# Battery_Management.net
KiCad netlist of a schematic drawn in Altium Designer
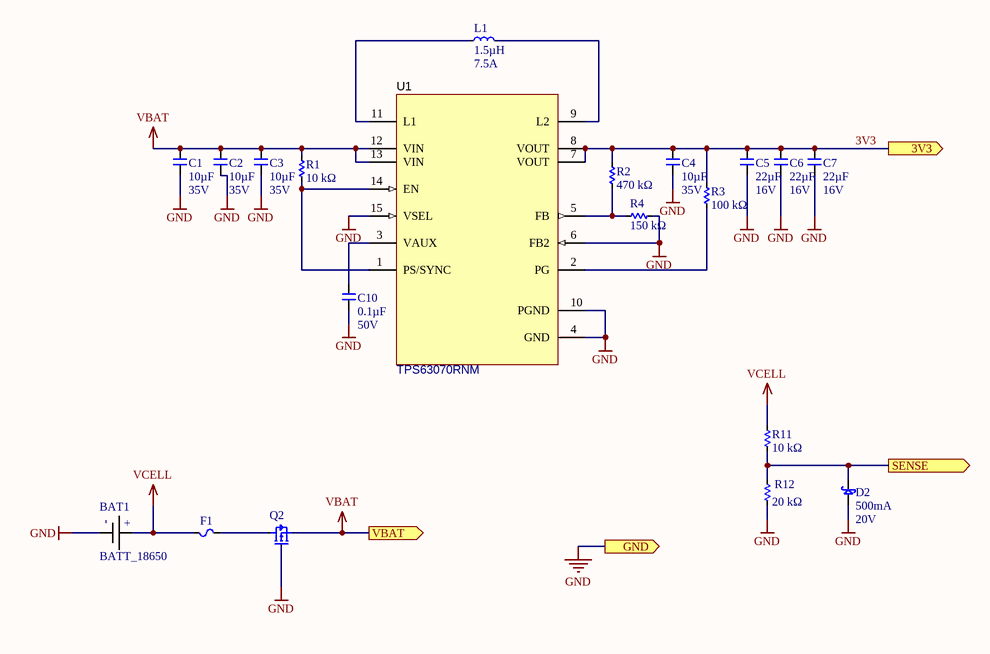
[diagram p0: Battery_Management.SchDoc]

(export (version "E")
  (design (tool "Eeschema 10.0.6"))
  (components
    (comp (ref "BAT1")
      (value "BATT_18650")
      (footprint "BATT_18650_KEYSTONE_1042_VIAS")
      (description "Dual Lithium Ion Cell Holder")
      (fields
        (field (name "MANUFACTURER") "Keystone Electronics")
        (field (name "MANUFACTURER PART NUMBER") "1048P")
      )
      (libsource (lib "Stanford Student Space Initiative") (part "BATT_18650"))
    )
    (comp (ref "C1")
      (value "490-13248-1-ND")
      (footprint "C0603")
      (description "CAP CER 10UF 35V X5R 0603 20%")
      (fields
        (field (name "CAPACITANCE (SHORTHAND)") "10µF")
        (field (name "RATED VOLTAGE") "35V")
        (field (name "MANUFACTURER") "Murata Electronics North America")
      )
      (libsource (lib "Stanford Student Space Initiative") (part "__template_cap"))
    )
    (comp (ref "C2")
      (value "490-13248-1-ND")
      (footprint "C0603")
      (description "CAP CER 10UF 35V X5R 0603 20%")
      (fields
        (field (name "CAPACITANCE (SHORTHAND)") "10µF")
        (field (name "RATED VOLTAGE") "35V")
        (field (name "MANUFACTURER") "Murata Electronics North America")
      )
      (libsource (lib "Stanford Student Space Initiative") (part "__template_cap"))
    )
    (comp (ref "C3")
      (value "490-13248-1-ND")
      (footprint "C0603")
      (description "CAP CER 10UF 35V X5R 0603 20%")
      (fields
        (field (name "CAPACITANCE (SHORTHAND)") "10µF")
        (field (name "RATED VOLTAGE") "35V")
        (field (name "MANUFACTURER") "Murata Electronics North America")
      )
      (libsource (lib "Stanford Student Space Initiative") (part "__template_cap"))
    )
    (comp (ref "C4")
      (value "490-13248-1-ND")
      (footprint "C0603")
      (description "CAP CER 10UF 35V X5R 0603 20%")
      (fields
        (field (name "CAPACITANCE (SHORTHAND)") "10µF")
        (field (name "RATED VOLTAGE") "35V")
        (field (name "MANUFACTURER") "Murata Electronics North America")
      )
      (libsource (lib "Stanford Student Space Initiative") (part "__template_cap"))
    )
    (comp (ref "C5")
      (value "1276-7076-1-ND")
      (footprint "C0603")
      (description "CAP CER 22UF 16V X5R 0603 20%")
      (fields
        (field (name "CAPACITANCE (SHORTHAND)") "22µF")
        (field (name "RATED VOLTAGE") "16V")
        (field (name "MANUFACTURER") "Samsung Electro-Mechanics")
      )
      (libsource (lib "Stanford Student Space Initiative") (part "__template_cap"))
    )
    (comp (ref "C6")
      (value "1276-7076-1-ND")
      (footprint "C0603")
      (description "CAP CER 22UF 16V X5R 0603 20%")
      (fields
        (field (name "CAPACITANCE (SHORTHAND)") "22µF")
        (field (name "RATED VOLTAGE") "16V")
        (field (name "MANUFACTURER") "Samsung Electro-Mechanics")
      )
      (libsource (lib "Stanford Student Space Initiative") (part "__template_cap"))
    )
    (comp (ref "C7")
      (value "1276-7076-1-ND")
      (footprint "C0603")
      (description "CAP CER 22UF 16V X5R 0603 20%")
      (fields
        (field (name "CAPACITANCE (SHORTHAND)") "22µF")
        (field (name "RATED VOLTAGE") "16V")
        (field (name "MANUFACTURER") "Samsung Electro-Mechanics")
      )
      (libsource (lib "Stanford Student Space Initiative") (part "__template_cap"))
    )
    (comp (ref "C10")
      (value "490-1519-1-ND")
      (footprint "C0603")
      (description "CAP CER 0603 0.1µF X7R 50V 10%")
      (fields
        (field (name "CAPACITANCE (SHORTHAND)") "0.1µF")
        (field (name "RATED VOLTAGE") "50V")
        (field (name "MANUFACTURER") "Murata Electronics North America")
      )
      (libsource (lib "Stanford Student Space Initiative") (part "__template_cap"))
    )
    (comp (ref "D2")
      (value "Symbol")
      (footprint "SOD123")
      (description "DIODE SCHOTTKY 0.5A 20V SOD-123")
      (fields
        (field (name "MANUFACTURER") "Fairchild Semiconductor")
        (field (name "MANUFACTURER PART NUMBER") "MBR0520L")
        (field (name "CURRENT - AVERAGE RECTIFIED (IO)") "500mA")
        (field (name "VOLTAGE - DC REVERSE (VR) (MAX)") "20V")
      )
      (libsource (lib "") (part "Symbol_2"))
    )
    (comp (ref "F1") (value "Symbol") (footprint "R1206") (libsource (lib "") (part "Symbol_1")))
    (comp (ref "L1")
      (value "Symbol")
      (footprint "SMD5230")
      (description "INDUCTOR POWER 1.5UH 7.5A SMD")
      (fields
        (field (name "MANUFACTURER") "Vishay Dale")
        (field (name "MANUFACTURER PART NUMBER") "IHLP2020CZER1R5M11")
        (field (name "INDUCTANCE") "1.5µH")
        (field (name "CURRENT RATING") "7.5A")
      )
      (libsource (lib "Stanford Student Space Initiative") (part "Symbol"))
    )
    (comp (ref "Q2")
      (value "PFET_SI7615ADN-T1")
      (footprint "POWERPAK_1212-8_SINGLE")
      (description "MOSFET P-CH 20V 35A PPK")
      (fields
        (field (name "MANUFACTURER PART NUMBER") "SI7615ADN-T1-GE3")
        (field (name "MANUFACTURER") "Vishay Siliconix")
      )
      (libsource (lib "Stanford Student Space Initiative") (part "PFET_SI7615ADN-T1"))
    )
    (comp (ref "R1")
      (value "311-10.0KHRCT-ND")
      (footprint "R0603")
      (description "RES SMD 10K OHM 1% 1/10W 0603")
      (fields
        (field (name "RESISTANCE") "10 kΩ")
        (field (name "MANUFACTURER PART NUMBER") "RC0603FR-0710KL")
        (field (name "MANUFACTURER") "Yageo")
      )
      (libsource (lib "Stanford Student Space Initiative") (part "__template_resistor"))
    )
    (comp (ref "R2")
      (value "311-470KHRCT-ND")
      (footprint "R0603")
      (description "RES SMD 470K OHM 1% 1/10W 0603")
      (fields
        (field (name "MANUFACTURER PART NUMBER") "RC0603FR-07470KL")
        (field (name "MANUFACTURER") "Yageo")
        (field (name "RESISTANCE") "470 kΩ")
      )
      (libsource (lib "Stanford Student Space Initiative") (part "__template_resistor"))
    )
    (comp (ref "R3")
      (value "311-100KHRCT-ND")
      (footprint "R0603")
      (description "RES SMD 100K OHM 1% 1/10W 0603")
      (fields
        (field (name "MANUFACTURER PART NUMBER") "RC0603FR-07100KL")
        (field (name "MANUFACTURER") "Yageo")
        (field (name "RESISTANCE") "100 kΩ")
      )
      (libsource (lib "Stanford Student Space Initiative") (part "__template_resistor"))
    )
    (comp (ref "R4")
      (value "311-150KHRCT-ND")
      (footprint "R0603")
      (description "RES SMD 150K OHM 1% 1/10W 0603")
      (fields
        (field (name "MANUFACTURER PART NUMBER") "RC0603FR-07150KL")
        (field (name "MANUFACTURER") "Yageo")
        (field (name "RESISTANCE") "150 kΩ")
      )
      (libsource (lib "Stanford Student Space Initiative") (part "__template_resistor"))
    )
    (comp (ref "R11")
      (value "311-10.0KHRCT-ND")
      (footprint "R0603")
      (description "RES SMD 10K OHM 1% 1/10W 0603")
      (fields
        (field (name "RESISTANCE") "10 kΩ")
        (field (name "MANUFACTURER PART NUMBER") "RC0603FR-0710KL")
        (field (name "MANUFACTURER") "Yageo")
      )
      (libsource (lib "Stanford Student Space Initiative") (part "__template_resistor"))
    )
    (comp (ref "R12")
      (value "311-20.0KHRCT-ND")
      (footprint "R0603")
      (description "RES SMD 20K OHM 1% 1/10W 0603")
      (fields
        (field (name "RESISTANCE") "20 kΩ")
        (field (name "MANUFACTURER PART NUMBER") "RC0603FR-0720KL")
        (field (name "MANUFACTURER") "Yageo")
      )
      (libsource (lib "Stanford Student Space Initiative") (part "__template_resistor"))
    )
    (comp (ref "U1")
      (value "TPS63070RNM")
      (footprint "TPS63070")
      (description "BUCKBOOST TPS63070RNM, RNM0015A")
      (fields
        (field (name "MANUFACTURER") "Texas Instruments")
        (field (name "MANUFACTURER PART NUMBER") "TPS63070RNMR")
      )
      (libsource (lib "Stanford Student Space Initiative") (part "TPS63070RNM"))
    )
  )
  (nets
    (net (code "1") (name "/3V3") (class "Default")
      (node (ref "C4") (pin "1") (pintype "passive"))
      (node (ref "C5") (pin "1") (pintype "passive"))
      (node (ref "C6") (pin "1") (pintype "passive"))
      (node (ref "C7") (pin "1") (pintype "passive"))
      (node (ref "R2") (pin "2") (pintype "passive"))
      (node (ref "R3") (pin "2") (pintype "passive"))
      (node (ref "U1") (pin "7") (pinfunction "VOUT_7") (pintype "power_in"))
      (node (ref "U1") (pin "8") (pinfunction "VOUT_8") (pintype "power_in"))
    )
    (net (code "2") (name "/SENSE") (class "Default")
      (node (ref "D2") (pin "2") (pintype "passive"))
      (node (ref "R11") (pin "1") (pintype "passive"))
      (node (ref "R12") (pin "2") (pintype "passive"))
    )
    (net (code "3") (name "GND") (class "Default")
      (node (ref "BAT1") (pin "CELL-") (pinfunction "CELL-_CELL-") (pintype "passive"))
      (node (ref "C1") (pin "2") (pintype "passive"))
      (node (ref "C10") (pin "2") (pintype "passive"))
      (node (ref "C2") (pin "2") (pintype "passive"))
      (node (ref "C3") (pin "2") (pintype "passive"))
      (node (ref "C4") (pin "2") (pintype "passive"))
      (node (ref "C5") (pin "2") (pintype "passive"))
      (node (ref "C6") (pin "2") (pintype "passive"))
      (node (ref "C7") (pin "2") (pintype "passive"))
      (node (ref "D2") (pin "1") (pintype "passive"))
      (node (ref "Q2") (pin "4") (pintype "passive"))
      (node (ref "R12") (pin "1") (pintype "passive"))
      (node (ref "R4") (pin "2") (pintype "passive"))
      (node (ref "U1") (pin "10") (pinfunction "PGND_10") (pintype "power_in"))
      (node (ref "U1") (pin "15") (pinfunction "VSEL_15") (pintype "input"))
      (node (ref "U1") (pin "4") (pinfunction "GND_4") (pintype "power_in"))
      (node (ref "U1") (pin "6") (pinfunction "FB2_6") (pintype "input"))
    )
    (net (code "4") (name "Net-(F1-Pad2)") (class "Default")
      (node (ref "F1") (pin "2") (pintype "passive"))
      (node (ref "Q2") (pin "5") (pintype "passive"))
    )
    (net (code "5") (name "Net-(U1-EN)") (class "Default")
      (node (ref "R1") (pin "1") (pintype "passive"))
      (node (ref "U1") (pin "1") (pinfunction "PS/SYNC_1") (pintype "passive"))
      (node (ref "U1") (pin "14") (pinfunction "EN_14") (pintype "input"))
    )
    (net (code "6") (name "Net-(U1-FB)") (class "Default")
      (node (ref "R2") (pin "1") (pintype "passive"))
      (node (ref "R4") (pin "1") (pintype "passive"))
      (node (ref "U1") (pin "5") (pinfunction "FB_5") (pintype "output"))
    )
    (net (code "7") (name "Net-(U1-L1)") (class "Default")
      (node (ref "L1") (pin "1") (pintype "passive"))
      (node (ref "U1") (pin "11") (pinfunction "L1_11") (pintype "passive"))
    )
    (net (code "8") (name "Net-(U1-L2)") (class "Default")
      (node (ref "L1") (pin "2") (pintype "passive"))
      (node (ref "U1") (pin "9") (pinfunction "L2_9") (pintype "passive"))
    )
    (net (code "9") (name "Net-(U1-PG)") (class "Default")
      (node (ref "R3") (pin "1") (pintype "passive"))
      (node (ref "U1") (pin "2") (pinfunction "PG_2") (pintype "open_collector"))
    )
    (net (code "10") (name "Net-(U1-VAUX)") (class "Default")
      (node (ref "C10") (pin "1") (pintype "passive"))
      (node (ref "U1") (pin "3") (pinfunction "VAUX_3") (pintype "passive"))
    )
    (net (code "11") (name "VBAT") (class "Default")
      (node (ref "C1") (pin "1") (pintype "passive"))
      (node (ref "C2") (pin "1") (pintype "passive"))
      (node (ref "C3") (pin "1") (pintype "passive"))
      (node (ref "Q2") (pin "1") (pintype "passive"))
      (node (ref "R1") (pin "2") (pintype "passive"))
      (node (ref "U1") (pin "12") (pinfunction "VIN_12") (pintype "power_in"))
      (node (ref "U1") (pin "13") (pinfunction "VIN_13") (pintype "power_in"))
    )
    (net (code "12") (name "VCELL") (class "Default")
      (node (ref "BAT1") (pin "CELL+") (pinfunction "CELL+_CELL+") (pintype "passive"))
      (node (ref "F1") (pin "1") (pintype "passive"))
      (node (ref "R11") (pin "2") (pintype "passive"))
    )
  )
)
